# mbox-001.net
KiCad netlist of a schematic drawn in EAGLE
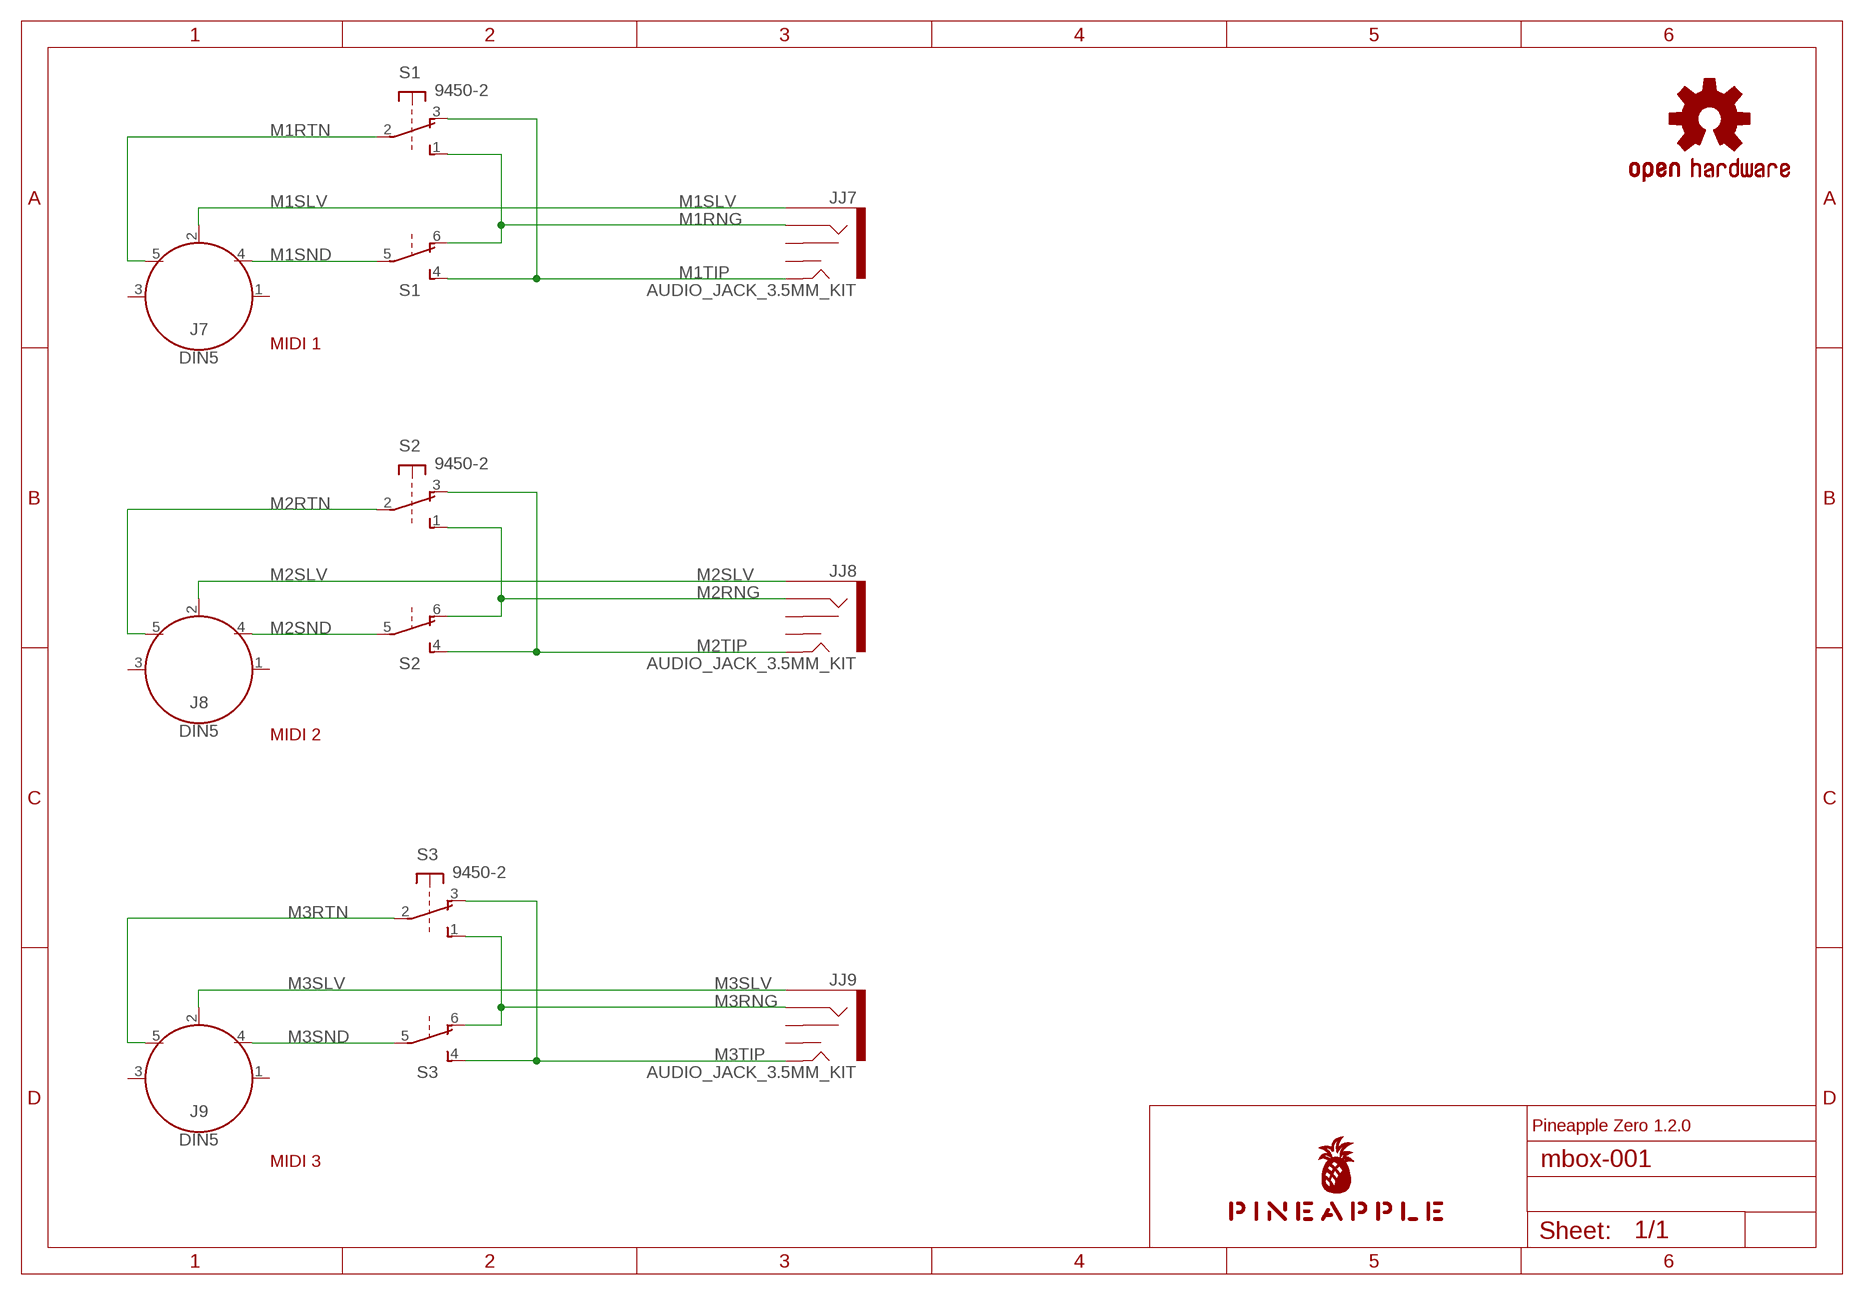
[diagram p0: schematic, sheet 1]

(export (version "E")
  (design (tool "Eeschema 10.0.6"))
  (components
    (comp (ref "J7")
      (value "DIN5")
      (footprint "eagle-import:DIN5-RA-PTH")
      (libsource (lib "eagle-import") (part "DIN5"))
    )
    (comp (ref "J8")
      (value "DIN5")
      (footprint "eagle-import:DIN5-RA-PTH")
      (libsource (lib "eagle-import") (part "DIN5"))
    )
    (comp (ref "J9")
      (value "DIN5")
      (footprint "eagle-import:DIN5-RA-PTH")
      (libsource (lib "eagle-import") (part "DIN5"))
    )
    (comp (ref "JJ7")
      (value "AUDIO_JACK_3.5MM_KIT")
      (footprint "eagle-import:AUDIO-JACK-KIT")
      (libsource (lib "eagle-import") (part "AUDIO_JACK_3.5MM_KIT"))
    )
    (comp (ref "JJ8")
      (value "AUDIO_JACK_3.5MM_KIT")
      (footprint "eagle-import:AUDIO-JACK-KIT")
      (libsource (lib "eagle-import") (part "AUDIO_JACK_3.5MM_KIT"))
    )
    (comp (ref "JJ9")
      (value "AUDIO_JACK_3.5MM_KIT")
      (footprint "eagle-import:AUDIO-JACK-KIT")
      (libsource (lib "eagle-import") (part "AUDIO_JACK_3.5MM_KIT"))
    )
    (comp (ref "LOGO1")
      (value "OSHW-LOGOS-COPPER")
      (footprint "eagle-import:OSHW-LOGO-S_COPPER")
      (libsource (lib "eagle-import") (part "OSHW-LOGOS-COPPER"))
    )
    (comp (ref "S1")
      (value "9450-2")
      (footprint "eagle-import:9450-2")
      (libsource (lib "eagle-import") (part "9450-2"))
    )
    (comp (ref "S2")
      (value "9450-2")
      (footprint "eagle-import:9450-2")
      (libsource (lib "eagle-import") (part "9450-2"))
    )
    (comp (ref "S3")
      (value "9450-2")
      (footprint "eagle-import:9450-2")
      (libsource (lib "eagle-import") (part "9450-2"))
    )
    (comp (ref "U$1")
      (value "PINEAPPLE450")
      (footprint "eagle-import:PINEAPPLE450")
      (libsource (lib "eagle-import") (part "PINEAPPLE450"))
    )
  )
  (nets
    (net (code "1") (name "/M1RNG") (class "Default")
      (node (ref "JJ7") (pin "RING") (pinfunction "RING_RING") (pintype "bidirectional"))
      (node (ref "S1") (pin "1") (pinfunction "S_1") (pintype "passive"))
      (node (ref "S1") (pin "6") (pinfunction "O_6") (pintype "passive"))
    )
    (net (code "2") (name "/M1RTN") (class "Default")
      (node (ref "J7") (pin "5") (pinfunction "5_5") (pintype "bidirectional"))
      (node (ref "S1") (pin "2") (pinfunction "P_2") (pintype "passive"))
    )
    (net (code "3") (name "/M1SLV") (class "Default")
      (node (ref "J7") (pin "2") (pinfunction "2_2") (pintype "bidirectional"))
      (node (ref "JJ7") (pin "SLEEVE") (pinfunction "SLEEVE_SLEEVE") (pintype "bidirectional"))
    )
    (net (code "4") (name "/M1SND") (class "Default")
      (node (ref "J7") (pin "4") (pinfunction "4_4") (pintype "bidirectional"))
      (node (ref "S1") (pin "5") (pinfunction "P_5") (pintype "passive"))
    )
    (net (code "5") (name "/M1TIP") (class "Default")
      (node (ref "JJ7") (pin "TIP") (pinfunction "TIP_TIP") (pintype "bidirectional"))
      (node (ref "S1") (pin "3") (pinfunction "O_3") (pintype "passive"))
      (node (ref "S1") (pin "4") (pinfunction "S_4") (pintype "passive"))
    )
    (net (code "6") (name "/M2RNG") (class "Default")
      (node (ref "JJ8") (pin "RING") (pinfunction "RING_RING") (pintype "bidirectional"))
      (node (ref "S2") (pin "1") (pinfunction "S_1") (pintype "passive"))
      (node (ref "S2") (pin "6") (pinfunction "O_6") (pintype "passive"))
    )
    (net (code "7") (name "/M2RTN") (class "Default")
      (node (ref "J8") (pin "5") (pinfunction "5_5") (pintype "bidirectional"))
      (node (ref "S2") (pin "2") (pinfunction "P_2") (pintype "passive"))
    )
    (net (code "8") (name "/M2SLV") (class "Default")
      (node (ref "J8") (pin "2") (pinfunction "2_2") (pintype "bidirectional"))
      (node (ref "JJ8") (pin "SLEEVE") (pinfunction "SLEEVE_SLEEVE") (pintype "bidirectional"))
    )
    (net (code "9") (name "/M2SND") (class "Default")
      (node (ref "J8") (pin "4") (pinfunction "4_4") (pintype "bidirectional"))
      (node (ref "S2") (pin "5") (pinfunction "P_5") (pintype "passive"))
    )
    (net (code "10") (name "/M2TIP") (class "Default")
      (node (ref "JJ8") (pin "TIP") (pinfunction "TIP_TIP") (pintype "bidirectional"))
      (node (ref "S2") (pin "3") (pinfunction "O_3") (pintype "passive"))
      (node (ref "S2") (pin "4") (pinfunction "S_4") (pintype "passive"))
    )
    (net (code "11") (name "/M3RNG") (class "Default")
      (node (ref "JJ9") (pin "RING") (pinfunction "RING_RING") (pintype "bidirectional"))
      (node (ref "S3") (pin "1") (pinfunction "S_1") (pintype "passive"))
      (node (ref "S3") (pin "6") (pinfunction "O_6") (pintype "passive"))
    )
    (net (code "12") (name "/M3RTN") (class "Default")
      (node (ref "J9") (pin "5") (pinfunction "5_5") (pintype "bidirectional"))
      (node (ref "S3") (pin "2") (pinfunction "P_2") (pintype "passive"))
    )
    (net (code "13") (name "/M3SLV") (class "Default")
      (node (ref "J9") (pin "2") (pinfunction "2_2") (pintype "bidirectional"))
      (node (ref "JJ9") (pin "SLEEVE") (pinfunction "SLEEVE_SLEEVE") (pintype "bidirectional"))
    )
    (net (code "14") (name "/M3SND") (class "Default")
      (node (ref "J9") (pin "4") (pinfunction "4_4") (pintype "bidirectional"))
      (node (ref "S3") (pin "5") (pinfunction "P_5") (pintype "passive"))
    )
    (net (code "15") (name "/M3TIP") (class "Default")
      (node (ref "JJ9") (pin "TIP") (pinfunction "TIP_TIP") (pintype "bidirectional"))
      (node (ref "S3") (pin "3") (pinfunction "O_3") (pintype "passive"))
      (node (ref "S3") (pin "4") (pinfunction "S_4") (pintype "passive"))
    )
    (net (code "16") (name "unconnected-(J7-Pad1)") (class "Default")
      (node (ref "J7") (pin "1") (pinfunction "1_1") (pintype "bidirectional"))
    )
    (net (code "17") (name "unconnected-(J7-Pad3)") (class "Default")
      (node (ref "J7") (pin "3") (pinfunction "3_3") (pintype "bidirectional"))
    )
    (net (code "18") (name "unconnected-(J8-Pad1)") (class "Default")
      (node (ref "J8") (pin "1") (pinfunction "1_1") (pintype "bidirectional"))
    )
    (net (code "19") (name "unconnected-(J8-Pad3)") (class "Default")
      (node (ref "J8") (pin "3") (pinfunction "3_3") (pintype "bidirectional"))
    )
    (net (code "20") (name "unconnected-(J9-Pad1)") (class "Default")
      (node (ref "J9") (pin "1") (pinfunction "1_1") (pintype "bidirectional"))
    )
    (net (code "21") (name "unconnected-(J9-Pad3)") (class "Default")
      (node (ref "J9") (pin "3") (pinfunction "3_3") (pintype "bidirectional"))
    )
    (net (code "22") (name "unconnected-(JJ7-PadRSH)") (class "Default")
      (node (ref "JJ7") (pin "RSH") (pinfunction "RSH_RSH") (pintype "bidirectional"))
    )
    (net (code "23") (name "unconnected-(JJ7-PadTSH)") (class "Default")
      (node (ref "JJ7") (pin "TSH") (pinfunction "TSH_TSH") (pintype "bidirectional"))
    )
    (net (code "24") (name "unconnected-(JJ8-PadRSH)") (class "Default")
      (node (ref "JJ8") (pin "RSH") (pinfunction "RSH_RSH") (pintype "bidirectional"))
    )
    (net (code "25") (name "unconnected-(JJ8-PadTSH)") (class "Default")
      (node (ref "JJ8") (pin "TSH") (pinfunction "TSH_TSH") (pintype "bidirectional"))
    )
    (net (code "26") (name "unconnected-(JJ9-PadRSH)") (class "Default")
      (node (ref "JJ9") (pin "RSH") (pinfunction "RSH_RSH") (pintype "bidirectional"))
    )
    (net (code "27") (name "unconnected-(JJ9-PadTSH)") (class "Default")
      (node (ref "JJ9") (pin "TSH") (pinfunction "TSH_TSH") (pintype "bidirectional"))
    )
  )
)
